# ISL29125_Breakout.net
KiCad netlist of a schematic drawn in EAGLE
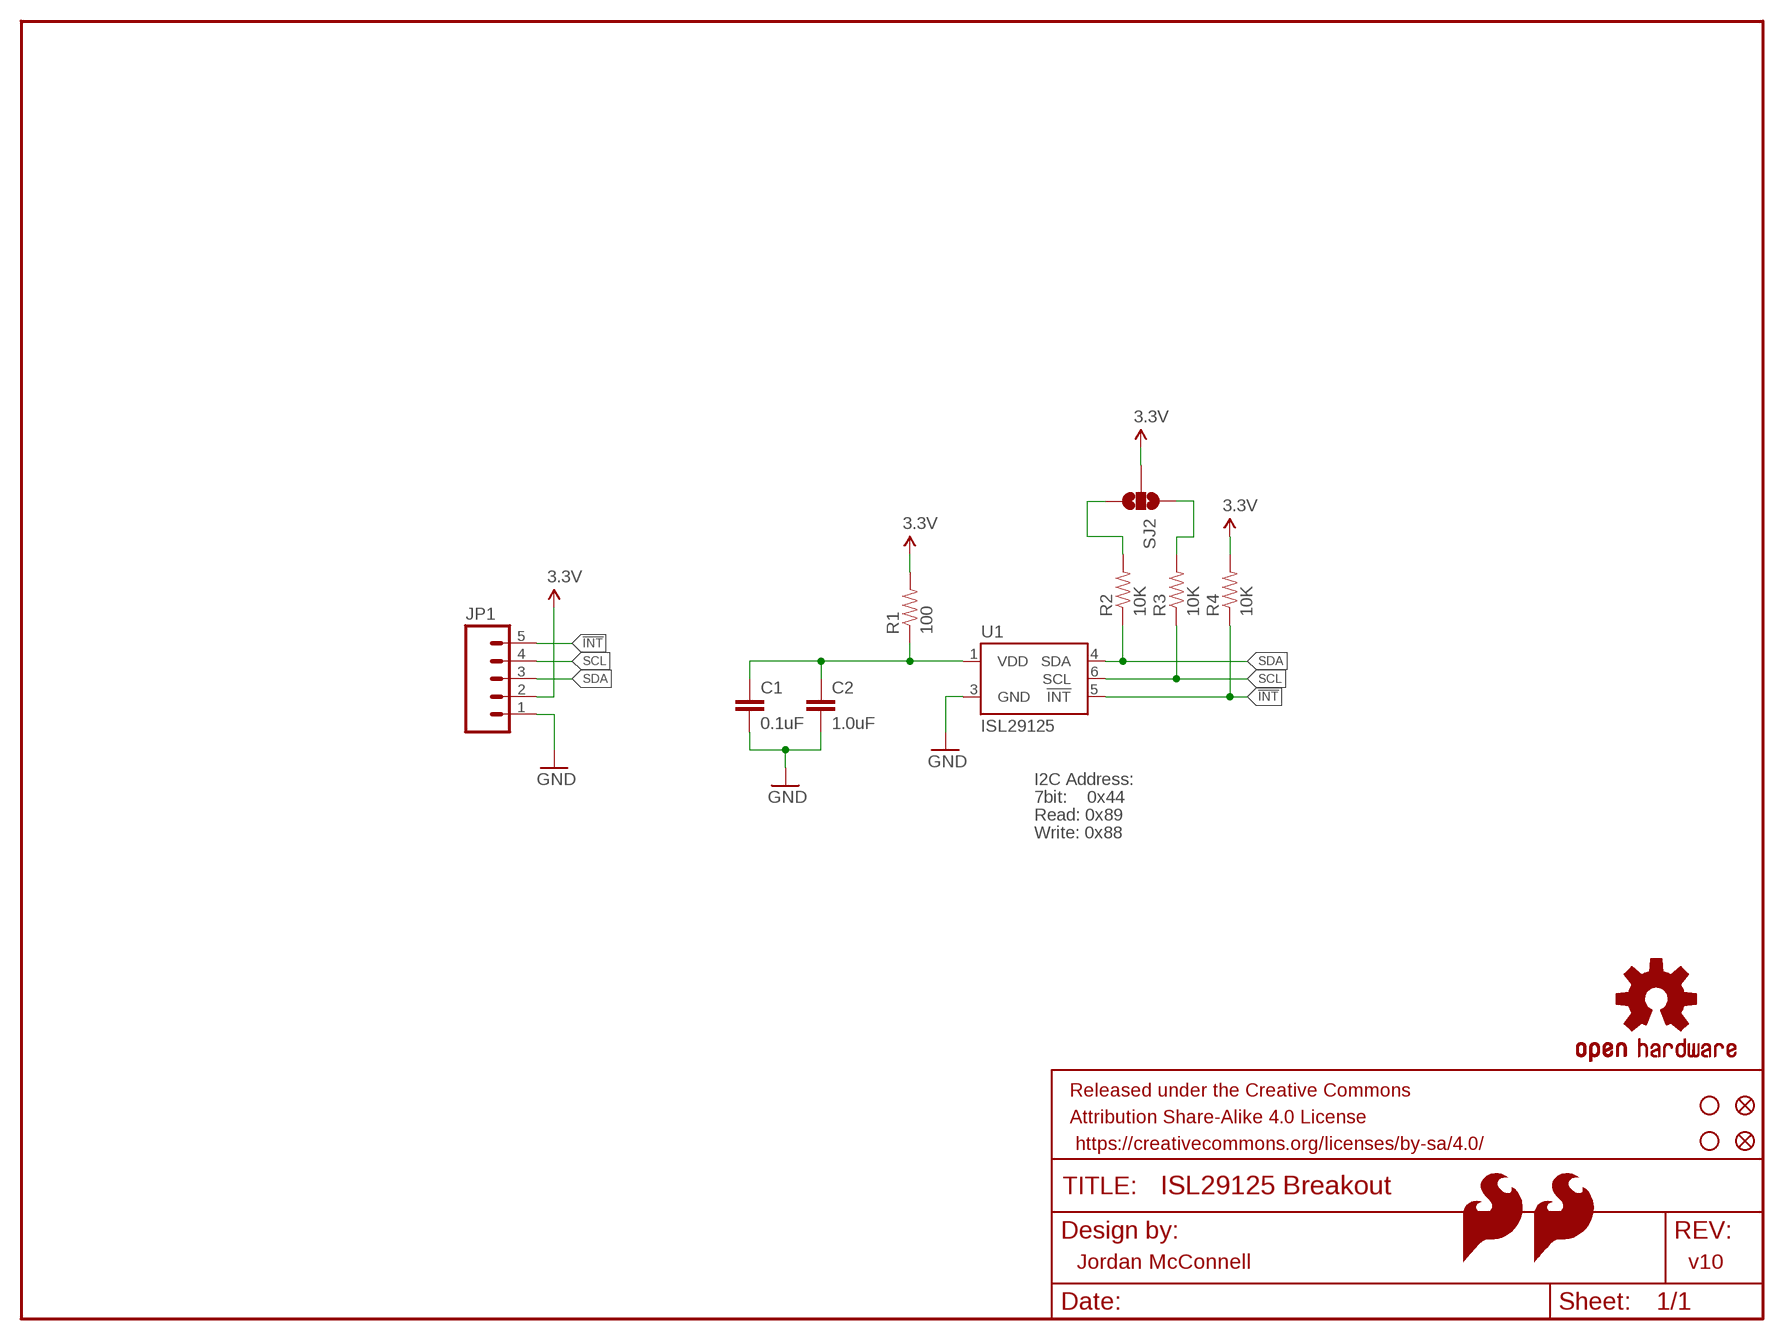
[diagram p0: schematic, sheet 1]

(export (version "E")
  (design (tool "Eeschema 10.0.6"))
  (components
    (comp (ref "C1")
      (value "0.1uF")
      (footprint "eagle-import:0603-CAP")
      (libsource (lib "eagle-import") (part "0.1UF-25V(+80/-20%)(0603)"))
    )
    (comp (ref "C2")
      (value "1.0uF")
      (footprint "eagle-import:0603-CAP")
      (libsource (lib "eagle-import") (part "1.0UF-16V-10%(0603)"))
    )
    (comp (ref "FID1")
      (value "FIDUCIAL1X2")
      (footprint "eagle-import:FIDUCIAL-1X2")
      (libsource (lib "eagle-import") (part "FIDUCIAL1X2"))
    )
    (comp (ref "FID2")
      (value "FIDUCIAL1X2")
      (footprint "eagle-import:FIDUCIAL-1X2")
      (libsource (lib "eagle-import") (part "FIDUCIAL1X2"))
    )
    (comp (ref "FRAME1")
      (value "FRAME-LETTER")
      (footprint "eagle-import:CREATIVE_COMMONS")
      (libsource (lib "eagle-import") (part "FRAME-LETTER"))
    )
    (comp (ref "JP1")
      (value "M05PTH")
      (footprint "eagle-import:1X05")
      (libsource (lib "eagle-import") (part "M05PTH"))
    )
    (comp (ref "LOGO2")
      (value "SFE_LOGO_FLAME.2_INCH")
      (footprint "eagle-import:SFE_LOGO_FLAME_.2")
      (libsource (lib "eagle-import") (part "SFE_LOGO_FLAME.2_INCH"))
    )
    (comp (ref "LOGO3")
      (value "OSHW-LOGOS")
      (footprint "eagle-import:OSHW-LOGO-S")
      (libsource (lib "eagle-import") (part "OSHW-LOGOS"))
    )
    (comp (ref "LOGO4")
      (value "SFE_LOGO_FLAME.2_INCH")
      (footprint "eagle-import:SFE_LOGO_FLAME_.2")
      (libsource (lib "eagle-import") (part "SFE_LOGO_FLAME.2_INCH"))
    )
    (comp (ref "R1")
      (value "100")
      (footprint "eagle-import:0603-RES")
      (libsource (lib "eagle-import") (part "100OHM1/10W1%(0603)"))
    )
    (comp (ref "R2")
      (value "10K")
      (footprint "eagle-import:0603-RES")
      (libsource (lib "eagle-import") (part "10KOHM1/10W1%(0603)0603"))
    )
    (comp (ref "R3")
      (value "10K")
      (footprint "eagle-import:0603-RES")
      (libsource (lib "eagle-import") (part "10KOHM1/10W1%(0603)0603"))
    )
    (comp (ref "R4")
      (value "10K")
      (footprint "eagle-import:0603-RES")
      (libsource (lib "eagle-import") (part "10KOHM1/10W1%(0603)0603"))
    )
    (comp (ref "SJ2")
      (value "SOLDERJUMPER_2WAYS")
      (footprint "eagle-import:SJ_3")
      (libsource (lib "eagle-import") (part "SOLDERJUMPER_2WAYS"))
    )
    (comp (ref "STANDOFF1")
      (value "STAND-OFF")
      (footprint "eagle-import:STAND-OFF")
      (libsource (lib "eagle-import") (part "STAND-OFF"))
    )
    (comp (ref "STANDOFF2")
      (value "STAND-OFF")
      (footprint "eagle-import:STAND-OFF")
      (libsource (lib "eagle-import") (part "STAND-OFF"))
    )
    (comp (ref "U1")
      (value "ISL29125")
      (footprint "eagle-import:ODFN-LD-6")
      (libsource (lib "eagle-import") (part "ISL29125"))
    )
  )
  (nets
    (net (code "1") (name "/~{INT}") (class "Default")
      (node (ref "JP1") (pin "5") (pinfunction "5_5") (pintype "passive"))
      (node (ref "R4") (pin "1") (pinfunction "1_1") (pintype "passive"))
      (node (ref "U1") (pin "5") (pinfunction "~{INT}_5") (pintype "bidirectional"))
    )
    (net (code "2") (name "3.3V") (class "Default")
      (node (ref "JP1") (pin "2") (pinfunction "2_2") (pintype "passive"))
      (node (ref "R1") (pin "2") (pinfunction "2_2") (pintype "passive"))
      (node (ref "R4") (pin "2") (pinfunction "2_2") (pintype "passive"))
      (node (ref "SJ2") (pin "2") (pinfunction "2_2") (pintype "passive"))
    )
    (net (code "3") (name "GND") (class "Default")
      (node (ref "C1") (pin "2") (pinfunction "2_2") (pintype "passive"))
      (node (ref "C2") (pin "2") (pinfunction "2_2") (pintype "passive"))
      (node (ref "JP1") (pin "1") (pinfunction "1_1") (pintype "passive"))
      (node (ref "U1") (pin "3") (pinfunction "GND_3") (pintype "bidirectional"))
    )
    (net (code "4") (name "Net-(R2-Pad2)") (class "Default")
      (node (ref "R2") (pin "2") (pinfunction "2_2") (pintype "passive"))
      (node (ref "SJ2") (pin "3") (pinfunction "3_3") (pintype "passive"))
    )
    (net (code "5") (name "Net-(R3-Pad2)") (class "Default")
      (node (ref "R3") (pin "2") (pinfunction "2_2") (pintype "passive"))
      (node (ref "SJ2") (pin "1") (pinfunction "1_1") (pintype "passive"))
    )
    (net (code "6") (name "Net-(U1-VDD)") (class "Default")
      (node (ref "C1") (pin "1") (pinfunction "1_1") (pintype "passive"))
      (node (ref "C2") (pin "1") (pinfunction "1_1") (pintype "passive"))
      (node (ref "R1") (pin "1") (pinfunction "1_1") (pintype "passive"))
      (node (ref "U1") (pin "1") (pinfunction "VDD_1") (pintype "bidirectional"))
    )
    (net (code "7") (name "SCL") (class "Default")
      (node (ref "JP1") (pin "4") (pinfunction "4_4") (pintype "passive"))
      (node (ref "R3") (pin "1") (pinfunction "1_1") (pintype "passive"))
      (node (ref "U1") (pin "6") (pinfunction "SCL_6") (pintype "bidirectional"))
    )
    (net (code "8") (name "SDA") (class "Default")
      (node (ref "JP1") (pin "3") (pinfunction "3_3") (pintype "passive"))
      (node (ref "R2") (pin "1") (pinfunction "1_1") (pintype "passive"))
      (node (ref "U1") (pin "4") (pinfunction "SDA_4") (pintype "bidirectional"))
    )
  )
)
